# snc98_main_cpu.net
KiCad netlist of a schematic drawn in EAGLE
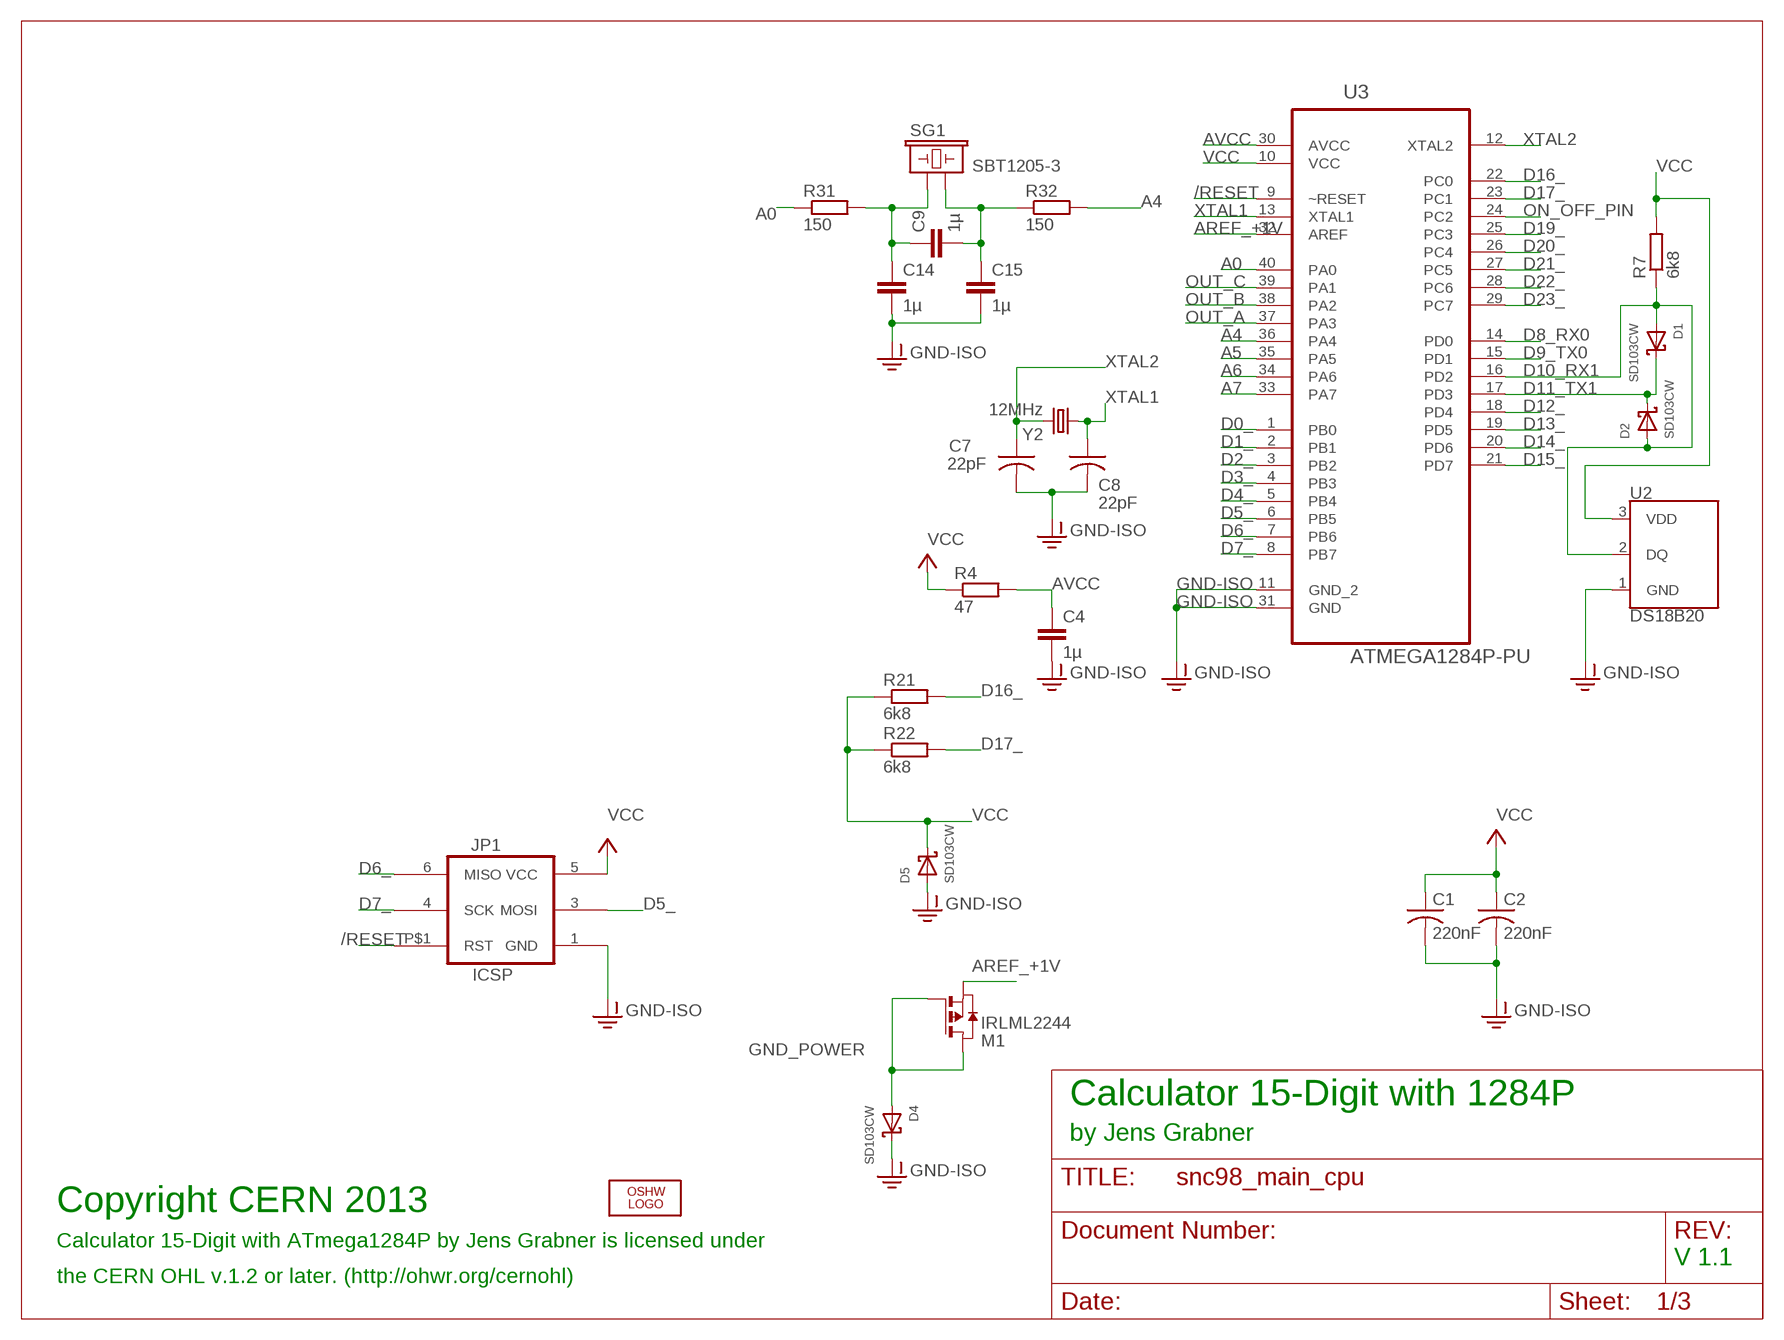
[diagram p0: schematic, sheet 1]
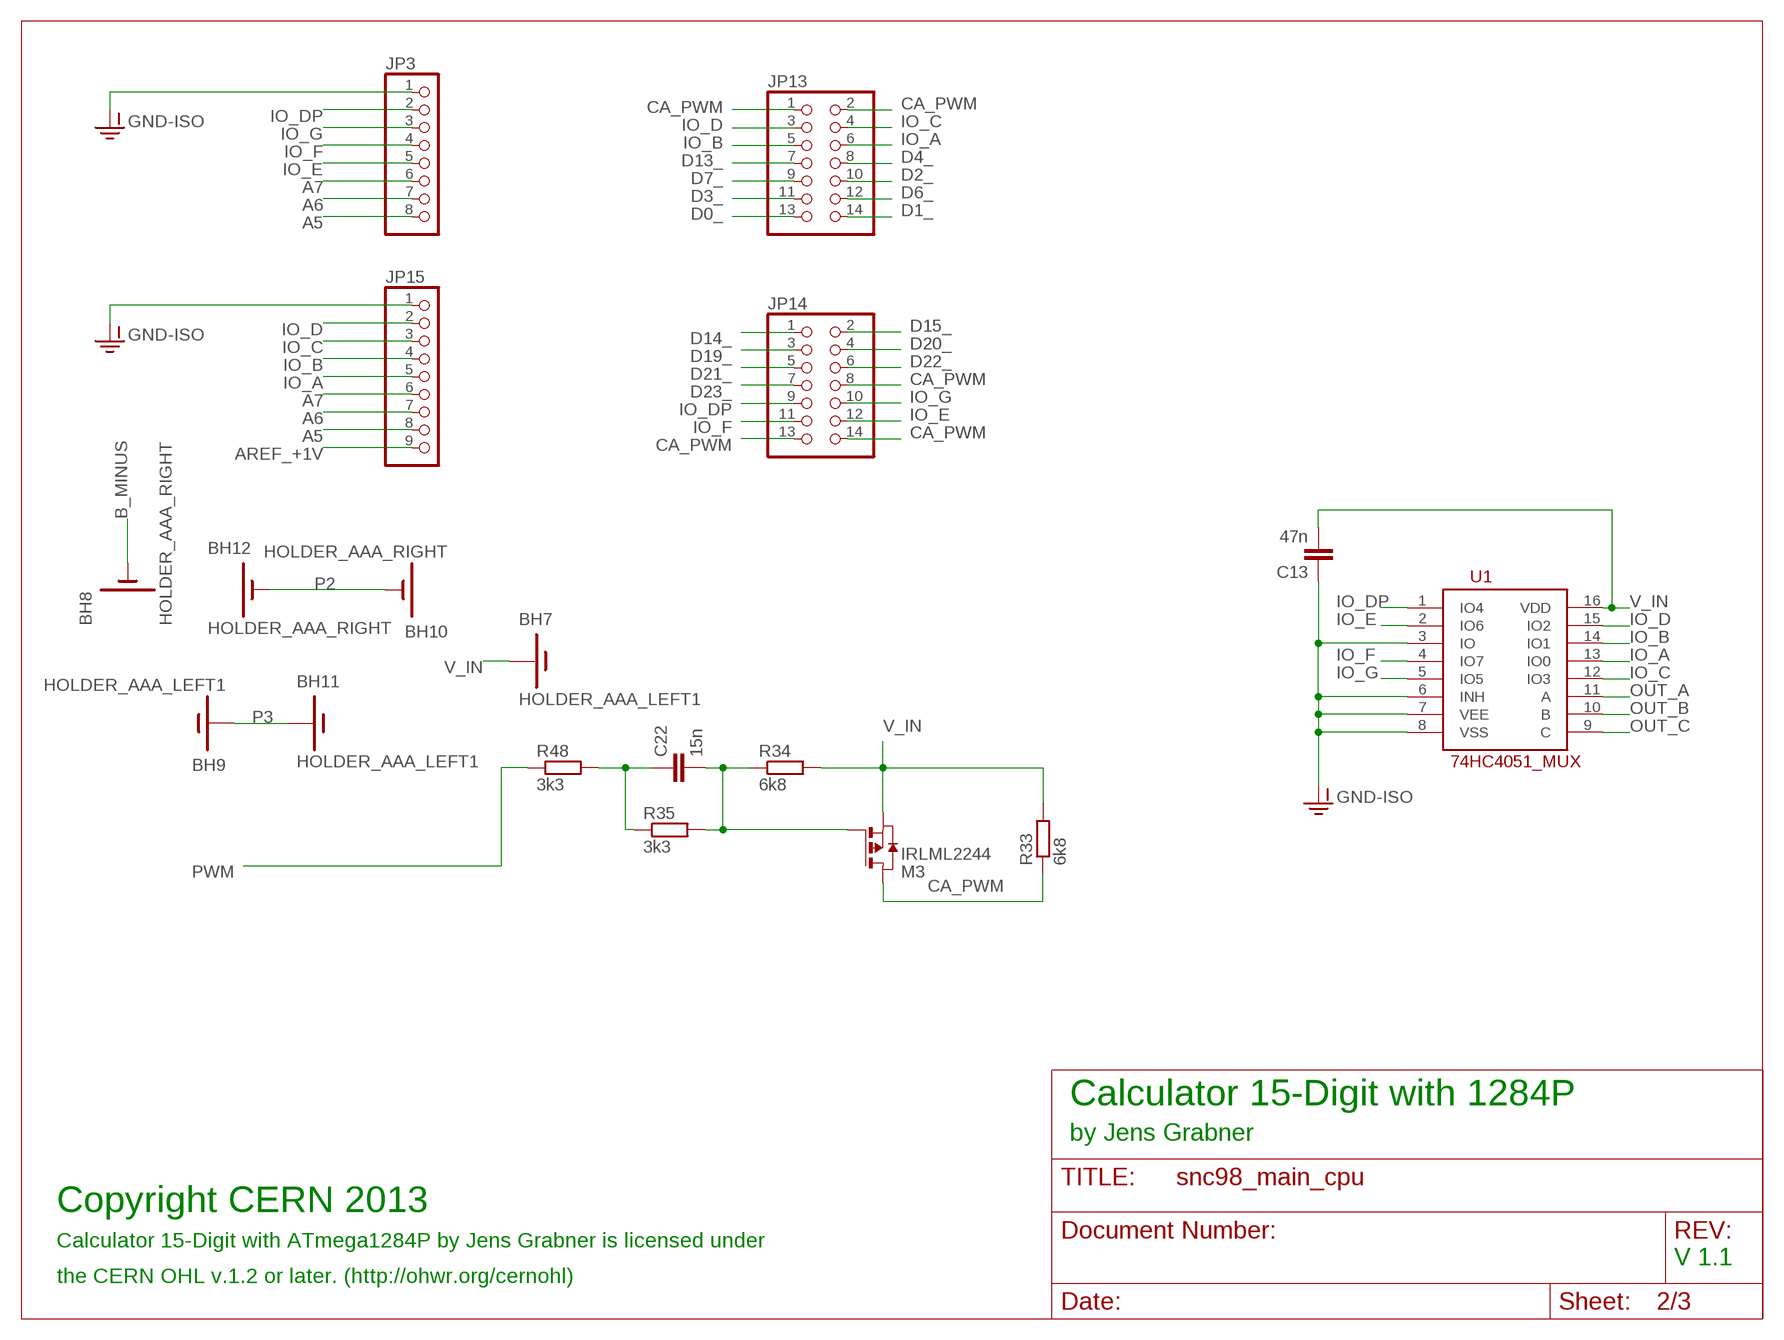
[diagram p1: schematic, sheet 2]
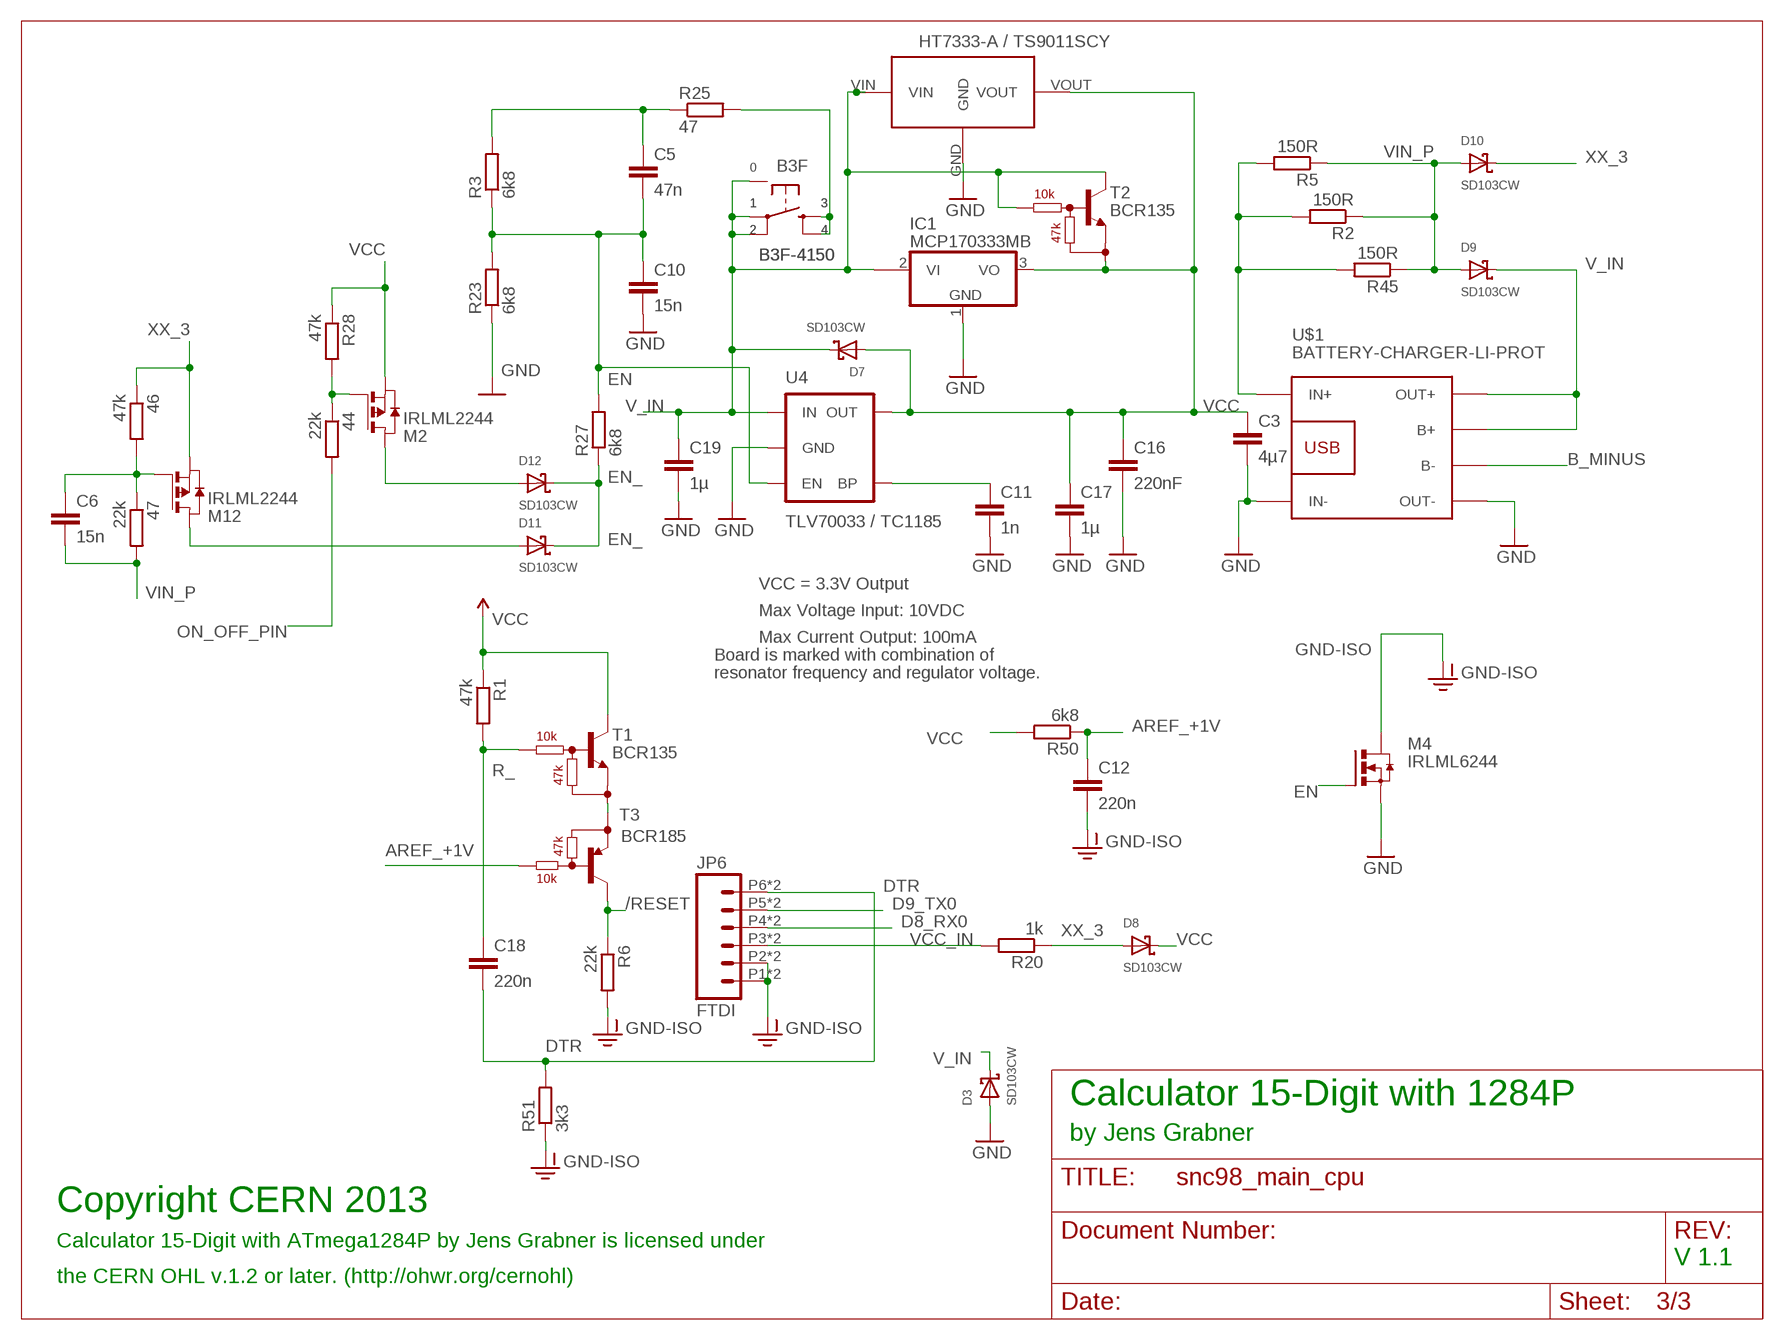
[diagram p2: schematic, sheet 3]

(export (version "E")
  (design (tool "Eeschema 10.0.6"))
  (components
    (comp (ref "44")
      (value "22k")
      (footprint "eagle-import:R1206")
      (libsource (lib "eagle-import") (part "R-EU_R1206"))
    )
    (comp (ref "46")
      (value "47k")
      (footprint "eagle-import:R1206")
      (libsource (lib "eagle-import") (part "R-EU_R1206"))
    )
    (comp (ref "47")
      (value "22k")
      (footprint "eagle-import:R1206")
      (libsource (lib "eagle-import") (part "R-EU_R1206"))
    )
    (comp (ref "C3")
      (value "4µ7")
      (footprint "eagle-import:C1206K")
      (libsource (lib "eagle-import") (part "C-EUC1206K"))
    )
    (comp (ref "C5")
      (value "47n")
      (footprint "eagle-import:C1206K")
      (fields (field (name "TME_EU") "CC0805KRX7R9473"))
      (libsource (lib "eagle-import") (part "C-EUC1206K"))
    )
    (comp (ref "C6")
      (value "15n")
      (footprint "eagle-import:C1206K")
      (fields (field (name "TME_EU") "CC0805KRX7R9153"))
      (libsource (lib "eagle-import") (part "C-EUC1206K"))
    )
    (comp (ref "C10")
      (value "15n")
      (footprint "eagle-import:C1206K")
      (fields (field (name "TME_EU") "CC0805KRX7R9153"))
      (libsource (lib "eagle-import") (part "C-EUC1206K"))
    )
    (comp (ref "C11")
      (value "1n")
      (footprint "eagle-import:0805")
      (libsource (lib "eagle-import") (part "CAP0805"))
    )
    (comp (ref "C12")
      (value "220n")
      (footprint "eagle-import:0805")
      (libsource (lib "eagle-import") (part "CAP0805"))
    )
    (comp (ref "C16")
      (value "220nF")
      (footprint "eagle-import:0805")
      (libsource (lib "eagle-import") (part "CAP0805"))
    )
    (comp (ref "C17")
      (value "1µ")
      (footprint "eagle-import:C1206K")
      (libsource (lib "eagle-import") (part "C-EUC1206K"))
    )
    (comp (ref "C18")
      (value "220n")
      (footprint "eagle-import:C1206K")
      (fields (field (name "TME_EU") "CC0805KPX7R7224"))
      (libsource (lib "eagle-import") (part "C-EUC1206K"))
    )
    (comp (ref "C19")
      (value "1µ")
      (footprint "eagle-import:C1206K")
      (libsource (lib "eagle-import") (part "C-EUC1206K"))
    )
    (comp (ref "D3")
      (value "SD103CW")
      (footprint "eagle-import:SOD-123F")
      (fields (field (name "MF") "MULTICOMP") (field (name "MPN") "SD103CW-7-F"))
      (libsource (lib "eagle-import") (part "DIODESOD-123F"))
    )
    (comp (ref "D7")
      (value "SD103CW")
      (footprint "eagle-import:SOD-123F")
      (fields (field (name "MF") "MULTICOMP") (field (name "MPN") "SD103CW-7-F"))
      (libsource (lib "eagle-import") (part "DIODESOD-123F"))
    )
    (comp (ref "D8")
      (value "SD103CW")
      (footprint "eagle-import:SOD-123F")
      (fields (field (name "MF") "MULTICOMP") (field (name "MPN") "SD103CW-7-F"))
      (libsource (lib "eagle-import") (part "DIODESOD-123F"))
    )
    (comp (ref "D9")
      (value "SD103CW")
      (footprint "eagle-import:SOD-123F")
      (fields (field (name "MF") "MULTICOMP") (field (name "MPN") "SD103CW-7-F"))
      (libsource (lib "eagle-import") (part "DIODESOD-123F"))
    )
    (comp (ref "D10")
      (value "SD103CW")
      (footprint "eagle-import:SOD-123F")
      (fields (field (name "MF") "MULTICOMP") (field (name "MPN") "SD103CW-7-F"))
      (libsource (lib "eagle-import") (part "DIODESOD-123F"))
    )
    (comp (ref "D11")
      (value "SD103CW")
      (footprint "eagle-import:SOD-123F")
      (fields (field (name "MF") "MULTICOMP") (field (name "MPN") "SD103CW-7-F"))
      (libsource (lib "eagle-import") (part "DIODESOD-123F"))
    )
    (comp (ref "D12")
      (value "SD103CW")
      (footprint "eagle-import:SOD-123F")
      (fields (field (name "MF") "MULTICOMP") (field (name "MPN") "SD103CW-7-F"))
      (libsource (lib "eagle-import") (part "DIODESOD-123F"))
    )
    (comp (ref "IC1")
      (value "MCP170333MB")
      (footprint "eagle-import:SOT89")
      (libsource (lib "eagle-import") (part "MCP1703MB33"))
    )
    (comp (ref "JP6")
      (value "FTDI")
      (footprint "eagle-import:1X06_LOCK")
      (libsource (lib "eagle-import") (part "M06LOCK"))
    )
    (comp (ref "M2")
      (value "IRLML2244")
      (footprint "eagle-import:SOT-23")
      (fields (field (name "MF") "INFINEON") (field (name "MPN") "IRLML2244TRPBF"))
      (libsource (lib "eagle-import") (part "IRLML6402"))
    )
    (comp (ref "M4")
      (value "IRLML6244")
      (footprint "eagle-import:SOT-23")
      (fields (field (name "MF") "INFINEON") (field (name "MPN") "IRLML6244TRPBF"))
      (libsource (lib "eagle-import") (part "IRLML2502M"))
    )
    (comp (ref "M12")
      (value "IRLML2244")
      (footprint "eagle-import:SOT-23")
      (fields (field (name "MF") "INFINEON") (field (name "MPN") "IRLML2244TRPBF"))
      (libsource (lib "eagle-import") (part "IRLML6402"))
    )
    (comp (ref "R1")
      (value "47k")
      (footprint "eagle-import:R1206")
      (libsource (lib "eagle-import") (part "R-EU_R1206"))
    )
    (comp (ref "R2")
      (value "150R")
      (footprint "eagle-import:0204_5")
      (libsource (lib "eagle-import") (part "R-EU_0204/5"))
    )
    (comp (ref "R3")
      (value "6k8")
      (footprint "eagle-import:R1206")
      (libsource (lib "eagle-import") (part "R-EU_R1206"))
    )
    (comp (ref "R5")
      (value "150R")
      (footprint "eagle-import:0207_10")
      (libsource (lib "eagle-import") (part "R-EU_0207/10"))
    )
    (comp (ref "R6")
      (value "22k")
      (footprint "eagle-import:R1206")
      (libsource (lib "eagle-import") (part "R-EU_R1206"))
    )
    (comp (ref "R20")
      (value "1k")
      (footprint "eagle-import:R1206")
      (libsource (lib "eagle-import") (part "R-EU_R1206"))
    )
    (comp (ref "R23")
      (value "6k8")
      (footprint "eagle-import:R1206")
      (libsource (lib "eagle-import") (part "R-EU_R1206"))
    )
    (comp (ref "R25")
      (value "47")
      (footprint "eagle-import:R1206")
      (libsource (lib "eagle-import") (part "R-EU_R1206"))
    )
    (comp (ref "R27")
      (value "6k8")
      (footprint "eagle-import:R1206")
      (libsource (lib "eagle-import") (part "R-EU_R1206"))
    )
    (comp (ref "R28")
      (value "47k")
      (footprint "eagle-import:R1206")
      (libsource (lib "eagle-import") (part "R-EU_R1206"))
    )
    (comp (ref "R45")
      (value "150R")
      (footprint "eagle-import:R1206")
      (libsource (lib "eagle-import") (part "R-EU_R1206"))
    )
    (comp (ref "R50")
      (value "6k8")
      (footprint "eagle-import:R1206")
      (libsource (lib "eagle-import") (part "R-EU_R1206"))
    )
    (comp (ref "R51")
      (value "3k3")
      (footprint "eagle-import:R1206")
      (libsource (lib "eagle-import") (part "R-EU_R1206"))
    )
    (comp (ref "S3")
      (value "B3F-4150")
      (footprint "eagle-import:TACTILE-PTH-12MM")
      (fields (field (name "MF") "OMRON") (field (name "MPN") "B3F4150"))
      (libsource (lib "eagle-import") (part "TACTILE_SWITCHTACTILE_SWITCH_PTH-12MM"))
    )
    (comp (ref "T1")
      (value "BCR135")
      (footprint "eagle-import:SOT23-BEC")
      (fields (field (name "MF") "INFINEON") (field (name "MPN") "BCR135E6327HTSA1"))
      (libsource (lib "eagle-import") (part "BCR135"))
    )
    (comp (ref "T2")
      (value "BCR135")
      (footprint "eagle-import:SOT23-BEC")
      (fields (field (name "MF") "INFINEON") (field (name "MPN") "BCR135E6327HTSA1"))
      (libsource (lib "eagle-import") (part "BCR135"))
    )
    (comp (ref "T3")
      (value "BCR185")
      (footprint "eagle-import:SOT23-R_INFINEON")
      (fields (field (name "MF") "ROHM") (field (name "MPN") "DTA114YKAT146"))
      (libsource (lib "eagle-import") (part "BCR185"))
    )
    (comp (ref "U$1")
      (value "BATTERY-CHARGER-LI-PROT")
      (footprint "eagle-import:BATTERY-CHARGER-LI-PROT")
      (libsource (lib "eagle-import") (part "BATTERY-CHARGER-LI-PROT"))
    )
    (comp (ref "U$3")
      (value "HT7333 / TS9011SCY")
      (footprint "eagle-import:SOT89")
      (libsource (lib "eagle-import") (part "HT7333"))
    )
    (comp (ref "U4")
      (value "TLV70033 / TC1185")
      (footprint "eagle-import:SOT23-5")
      (libsource (lib "eagle-import") (part "V_REG_LDOSMD"))
    )
    (comp (ref "C1")
      (value "220nF")
      (footprint "eagle-import:C1206K")
      (libsource (lib "eagle-import") (part "C-USC1206K"))
    )
    (comp (ref "C2")
      (value "220nF")
      (footprint "eagle-import:C1206K")
      (libsource (lib "eagle-import") (part "C-USC1206K"))
    )
    (comp (ref "C4")
      (value "1µ")
      (footprint "eagle-import:C1206K")
      (libsource (lib "eagle-import") (part "C-EUC1206K"))
    )
    (comp (ref "C7")
      (value "22pF")
      (footprint "eagle-import:C0805K")
      (libsource (lib "eagle-import") (part "C-USC0805K"))
    )
    (comp (ref "C8")
      (value "22pF")
      (footprint "eagle-import:C0805K")
      (libsource (lib "eagle-import") (part "C-USC0805K"))
    )
    (comp (ref "C9")
      (value "1µ")
      (footprint "eagle-import:C1206K")
      (libsource (lib "eagle-import") (part "C-EUC1206K"))
    )
    (comp (ref "C14")
      (value "1µ")
      (footprint "eagle-import:C1206K")
      (libsource (lib "eagle-import") (part "C-EUC1206K"))
    )
    (comp (ref "C15")
      (value "1µ")
      (footprint "eagle-import:C1206K")
      (libsource (lib "eagle-import") (part "C-EUC1206K"))
    )
    (comp (ref "D1")
      (value "SD103CW")
      (footprint "eagle-import:SOD-323")
      (fields (field (name "MF") "MULTICOMP") (field (name "MPN") "SD103CW-7-F"))
      (libsource (lib "eagle-import") (part "DIODESOD-323"))
    )
    (comp (ref "D2")
      (value "SD103CW")
      (footprint "eagle-import:SOD-123")
      (fields (field (name "MF") "MULTICOMP") (field (name "MPN") "SD103CW-7-F"))
      (libsource (lib "eagle-import") (part "DIODESOD-123"))
    )
    (comp (ref "D4")
      (value "SD103CW")
      (footprint "eagle-import:SOD-123F")
      (fields (field (name "MF") "MULTICOMP") (field (name "MPN") "SD103CW-7-F"))
      (libsource (lib "eagle-import") (part "DIODESOD-123F"))
    )
    (comp (ref "D5")
      (value "SD103CW")
      (footprint "eagle-import:SOD-123F")
      (fields (field (name "MF") "MULTICOMP") (field (name "MPN") "SD103CW-7-F"))
      (libsource (lib "eagle-import") (part "DIODESOD-123F"))
    )
    (comp (ref "JP1")
      (value "ICSP")
      (footprint "eagle-import:2X3_SMD_VERTICAL")
      (libsource (lib "eagle-import") (part "AVR_SPI_PRG_6"))
    )
    (comp (ref "LOGO1")
      (value "OSHW_LOGO_8MILX0150-NT")
      (footprint "eagle-import:OSHW_8X150_NOTEXT")
      (libsource (lib "eagle-import") (part "OSHW_LOGO_8MILX0150-NT"))
    )
    (comp (ref "M1")
      (value "IRLML2244")
      (footprint "eagle-import:SOT-23")
      (fields
        (field (name "MF") "INFINEON")
        (field (name "MPN") "IRLML2244TRPBF")
        (field (name "TME_EU") "DMG2305UX-7")
      )
      (libsource (lib "eagle-import") (part "IRLML6402"))
    )
    (comp (ref "R4")
      (value "47")
      (footprint "eagle-import:R1206")
      (libsource (lib "eagle-import") (part "R-EU_R1206"))
    )
    (comp (ref "R7")
      (value "6k8")
      (footprint "eagle-import:R1206")
      (libsource (lib "eagle-import") (part "R-EU_R1206"))
    )
    (comp (ref "R21")
      (value "6k8")
      (footprint "eagle-import:R1206")
      (libsource (lib "eagle-import") (part "R-EU_R1206"))
    )
    (comp (ref "R22")
      (value "6k8")
      (footprint "eagle-import:R1206")
      (libsource (lib "eagle-import") (part "R-EU_R1206"))
    )
    (comp (ref "R31")
      (value "150")
      (footprint "eagle-import:R1206")
      (libsource (lib "eagle-import") (part "R-EU_R1206"))
    )
    (comp (ref "R32")
      (value "150")
      (footprint "eagle-import:R1206")
      (libsource (lib "eagle-import") (part "R-EU_R1206"))
    )
    (comp (ref "SG1")
      (value "SBT1205-3")
      (footprint "eagle-import:BUZZER-12MM-NS")
      (libsource (lib "eagle-import") (part "BUZZERNS"))
    )
    (comp (ref "U2")
      (value "DS18B20")
      (footprint "eagle-import:TO-92-AMMO")
      (libsource (lib "eagle-import") (part "DS18B20"))
    )
    (comp (ref "U3")
      (value "ATMEGA1284P-PU")
      (footprint "eagle-import:DIP254P1524X483-40")
      (fields (field (name "MF") "MICROCHIP"))
      (libsource (lib "eagle-import") (part "ATMEGA1284P-PU"))
    )
    (comp (ref "Y2")
      (value "12MHz")
      (footprint "eagle-import:HC49U-V")
      (libsource (lib "eagle-import") (part "CRYSTALHC49UV"))
    )
    (comp (ref "BH7")
      (value "HOLDER_AAA_LEFT1")
      (footprint "eagle-import:BATTERY-AAA-LEFT")
      (libsource (lib "eagle-import") (part "HOLDER_AAA_LEFT1"))
    )
    (comp (ref "BH8")
      (value "HOLDER_AAA_RIGHT")
      (footprint "eagle-import:BATTERY-AAA-RIGHT")
      (libsource (lib "eagle-import") (part "HOLDER_AAA_RIGHT"))
    )
    (comp (ref "BH9")
      (value "HOLDER_AAA_LEFT1")
      (footprint "eagle-import:BATTERY-AAA-LEFT")
      (fields (field (name "TME_EU") "BC-0401"))
      (libsource (lib "eagle-import") (part "HOLDER_AAA_LEFT1"))
    )
    (comp (ref "BH10")
      (value "HOLDER_AAA_RIGHT")
      (footprint "eagle-import:BATTERY-AAA-RIGHT")
      (libsource (lib "eagle-import") (part "HOLDER_AAA_RIGHT"))
    )
    (comp (ref "BH11")
      (value "HOLDER_AAA_LEFT1")
      (footprint "eagle-import:BATTERY-AAA-LEFT")
      (libsource (lib "eagle-import") (part "HOLDER_AAA_LEFT1"))
    )
    (comp (ref "BH12")
      (value "HOLDER_AAA_RIGHT")
      (footprint "eagle-import:BATTERY-AAA-RIGHT")
      (libsource (lib "eagle-import") (part "HOLDER_AAA_RIGHT"))
    )
    (comp (ref "C13")
      (value "47n")
      (footprint "eagle-import:C1206K")
      (fields (field (name "TME_EU") "CC0805KRX7R9473"))
      (libsource (lib "eagle-import") (part "C-EUC1206K"))
    )
    (comp (ref "C22")
      (value "15n")
      (footprint "eagle-import:C1206K")
      (fields (field (name "TME_EU") "CC0805KRX7R9153"))
      (libsource (lib "eagle-import") (part "C-EUC1206K"))
    )
    (comp (ref "JP3")
      (value "PINHD-1X8CLEANBIG")
      (footprint "eagle-import:1X08-CLEANBIG")
      (libsource (lib "eagle-import") (part "PINHD-1X8CLEANBIG"))
    )
    (comp (ref "JP13")
      (value "PINHD-2X7")
      (footprint "eagle-import:2X07")
      (libsource (lib "eagle-import") (part "PINHD-2X7"))
    )
    (comp (ref "JP14")
      (value "PINHD-2X7")
      (footprint "eagle-import:2X07")
      (libsource (lib "eagle-import") (part "PINHD-2X7"))
    )
    (comp (ref "JP15")
      (value "PINHD-1X9")
      (footprint "eagle-import:1X09-BIG")
      (libsource (lib "eagle-import") (part "PINHD-1X9"))
    )
    (comp (ref "M3")
      (value "IRLML2244")
      (footprint "eagle-import:SOT-23")
      (fields (field (name "MF") "INFINEON") (field (name "MPN") "IRLML2244TRPBF"))
      (libsource (lib "eagle-import") (part "IRLML6402"))
    )
    (comp (ref "R33")
      (value "6k8")
      (footprint "eagle-import:R1206")
      (libsource (lib "eagle-import") (part "R-EU_R1206"))
    )
    (comp (ref "R34")
      (value "6k8")
      (footprint "eagle-import:R1206")
      (libsource (lib "eagle-import") (part "R-EU_R1206"))
    )
    (comp (ref "R35")
      (value "3k3")
      (footprint "eagle-import:R1206")
      (libsource (lib "eagle-import") (part "R-EU_R1206"))
    )
    (comp (ref "R48")
      (value "3k3")
      (footprint "eagle-import:R1206")
      (libsource (lib "eagle-import") (part "R-EU_R1206"))
    )
    (comp (ref "U1")
      (value "74HC4051_MUX")
      (footprint "eagle-import:SO16")
      (libsource (lib "eagle-import") (part "74HC4051_MUX"))
    )
  )
  (nets
    (net (code "1") (name "A0") (class "Default")
      (node (ref "R31") (pin "1") (pinfunction "1_1") (pintype "passive"))
      (node (ref "U3") (pin "40") (pinfunction "PA0_40") (pintype "bidirectional"))
    )
    (net (code "2") (name "A4") (class "Default")
      (node (ref "R32") (pin "2") (pinfunction "2_2") (pintype "passive"))
      (node (ref "U3") (pin "36") (pinfunction "PA4_36") (pintype "bidirectional"))
    )
    (net (code "3") (name "A5") (class "Default")
      (node (ref "JP15") (pin "8") (pinfunction "8_8") (pintype "passive"))
      (node (ref "JP3") (pin "8") (pinfunction "8_8") (pintype "passive"))
      (node (ref "U3") (pin "35") (pinfunction "PA5_35") (pintype "bidirectional"))
    )
    (net (code "4") (name "A6") (class "Default")
      (node (ref "JP15") (pin "7") (pinfunction "7_7") (pintype "passive"))
      (node (ref "JP3") (pin "7") (pinfunction "7_7") (pintype "passive"))
      (node (ref "U3") (pin "34") (pinfunction "PA6_34") (pintype "bidirectional"))
    )
    (net (code "5") (name "A7") (class "Default")
      (node (ref "JP15") (pin "6") (pinfunction "6_6") (pintype "passive"))
      (node (ref "JP3") (pin "6") (pinfunction "6_6") (pintype "passive"))
      (node (ref "U3") (pin "33") (pinfunction "PA7_33") (pintype "bidirectional"))
    )
    (net (code "6") (name "AREF_+1V") (class "Default")
      (node (ref "C12") (pin "3") (pinfunction "1_3") (pintype "passive"))
      (node (ref "JP15") (pin "9") (pinfunction "9_9") (pintype "passive"))
      (node (ref "M1") (pin "2") (pinfunction "S_2") (pintype "passive"))
      (node (ref "R50") (pin "1") (pinfunction "1_1") (pintype "passive"))
      (node (ref "T3") (pin "B") (pinfunction "B_B") (pintype "passive"))
      (node (ref "U3") (pin "32") (pinfunction "AREF_32") (pintype "input"))
    )
    (net (code "7") (name "AVCC") (class "Default")
      (node (ref "C4") (pin "1") (pinfunction "1_1") (pintype "passive"))
      (node (ref "R4") (pin "2") (pinfunction "2_2") (pintype "passive"))
      (node (ref "U3") (pin "30") (pinfunction "AVCC_30") (pintype "power_in"))
    )
    (net (code "8") (name "B_MINUS") (class "Default")
      (node (ref "BH8") (pin "M1") (pinfunction "-_M1") (pintype "power_in"))
      (node (ref "BH8") (pin "M2") (pinfunction "-_M2") (pintype "power_in"))
      (node (ref "BH8") (pin "M3") (pinfunction "-_M3") (pintype "power_in"))
      (node (ref "BH8") (pin "M4") (pinfunction "-_M4") (pintype "power_in"))
      (node (ref "U$1") (pin "B-") (pinfunction "B-_B-") (pintype "bidirectional"))
    )
    (net (code "9") (name "CA_PWM") (class "Default")
      (node (ref "JP13") (pin "1") (pinfunction "1_1") (pintype "passive"))
      (node (ref "JP13") (pin "2") (pinfunction "2_2") (pintype "passive"))
      (node (ref "JP14") (pin "13") (pinfunction "13_13") (pintype "passive"))
      (node (ref "JP14") (pin "14") (pinfunction "14_14") (pintype "passive"))
      (node (ref "JP14") (pin "8") (pinfunction "8_8") (pintype "passive"))
      (node (ref "M3") (pin "3") (pinfunction "D_3") (pintype "passive"))
      (node (ref "R33") (pin "1") (pinfunction "1_1") (pintype "passive"))
    )
    (net (code "10") (name "D0_") (class "Default")
      (node (ref "JP13") (pin "13") (pinfunction "13_13") (pintype "passive"))
      (node (ref "U3") (pin "1") (pinfunction "PB0_1") (pintype "bidirectional"))
    )
    (net (code "11") (name "D1_") (class "Default")
      (node (ref "JP13") (pin "14") (pinfunction "14_14") (pintype "passive"))
      (node (ref "U3") (pin "2") (pinfunction "PB1_2") (pintype "bidirectional"))
    )
    (net (code "12") (name "D2_") (class "Default")
      (node (ref "JP13") (pin "10") (pinfunction "10_10") (pintype "passive"))
      (node (ref "U3") (pin "3") (pinfunction "PB2_3") (pintype "bidirectional"))
    )
    (net (code "13") (name "D3_") (class "Default")
      (node (ref "JP13") (pin "11") (pinfunction "11_11") (pintype "passive"))
      (node (ref "U3") (pin "4") (pinfunction "PB3_4") (pintype "bidirectional"))
    )
    (net (code "14") (name "D4_") (class "Default")
      (node (ref "JP13") (pin "8") (pinfunction "8_8") (pintype "passive"))
      (node (ref "U3") (pin "5") (pinfunction "PB4_5") (pintype "bidirectional"))
    )
    (net (code "15") (name "D5_") (class "Default")
      (node (ref "JP1") (pin "3") (pinfunction "MOSI_3") (pintype "passive"))
      (node (ref "U3") (pin "6") (pinfunction "PB5_6") (pintype "bidirectional"))
    )
    (net (code "16") (name "D6_") (class "Default")
      (node (ref "JP1") (pin "6") (pinfunction "MISO_6") (pintype "passive"))
      (node (ref "JP13") (pin "12") (pinfunction "12_12") (pintype "passive"))
      (node (ref "U3") (pin "7") (pinfunction "PB6_7") (pintype "bidirectional"))
    )
    (net (code "17") (name "D7_") (class "Default")
      (node (ref "JP1") (pin "4") (pinfunction "SCK_4") (pintype "passive"))
      (node (ref "JP13") (pin "9") (pinfunction "9_9") (pintype "passive"))
      (node (ref "U3") (pin "8") (pinfunction "PB7_8") (pintype "bidirectional"))
    )
    (net (code "18") (name "D8_RX0") (class "Default")
      (node (ref "JP6") (pin "P4") (pinfunction "4_P4") (pintype "passive"))
      (node (ref "JP6") (pin "P4A") (pinfunction "4_P4A") (pintype "passive"))
      (node (ref "U3") (pin "14") (pinfunction "PD0_14") (pintype "bidirectional"))
    )
    (net (code "19") (name "D9_TX0") (class "Default")
      (node (ref "JP6") (pin "P5") (pinfunction "5_P5") (pintype "passive"))
      (node (ref "JP6") (pin "P5A") (pinfunction "5_P5A") (pintype "passive"))
      (node (ref "U3") (pin "15") (pinfunction "PD1_15") (pintype "bidirectional"))
    )
    (net (code "20") (name "D10_RX1") (class "Default")
      (node (ref "D1") (pin "A") (pinfunction "A_A") (pintype "passive"))
      (node (ref "D2") (pin "A") (pinfunction "A_A") (pintype "passive"))
      (node (ref "R7") (pin "1") (pinfunction "1_1") (pintype "passive"))
      (node (ref "U2") (pin "2") (pinfunction "DQ_2") (pintype "bidirectional"))
      (node (ref "U3") (pin "16") (pinfunction "PD2_16") (pintype "bidirectional"))
    )
    (net (code "21") (name "D11_TX1") (class "Default")
      (node (ref "D1") (pin "C") (pinfunction "C_C") (pintype "passive"))
      (node (ref "D2") (pin "C") (pinfunction "C_C") (pintype "passive"))
      (node (ref "U3") (pin "17") (pinfunction "PD3_17") (pintype "bidirectional"))
    )
    (net (code "22") (name "D12_") (class "Default")
      (node (ref "U3") (pin "18") (pinfunction "PD4_18") (pintype "bidirectional"))
    )
    (net (code "23") (name "D13_") (class "Default")
      (node (ref "JP13") (pin "7") (pinfunction "7_7") (pintype "passive"))
      (node (ref "U3") (pin "19") (pinfunction "PD5_19") (pintype "bidirectional"))
    )
    (net (code "24") (name "D14_") (class "Default")
      (node (ref "JP14") (pin "1") (pinfunction "1_1") (pintype "passive"))
      (node (ref "U3") (pin "20") (pinfunction "PD6_20") (pintype "bidirectional"))
    )
    (net (code "25") (name "D15_") (class "Default")
      (node (ref "JP14") (pin "2") (pinfunction "2_2") (pintype "passive"))
      (node (ref "U3") (pin "21") (pinfunction "PD7_21") (pintype "bidirectional"))
    )
    (net (code "26") (name "D16_") (class "Default")
      (node (ref "R21") (pin "2") (pinfunction "2_2") (pintype "passive"))
      (node (ref "U3") (pin "22") (pinfunction "PC0_22") (pintype "bidirectional"))
    )
    (net (code "27") (name "D17_") (class "Default")
      (node (ref "R22") (pin "2") (pinfunction "2_2") (pintype "passive"))
      (node (ref "U3") (pin "23") (pinfunction "PC1_23") (pintype "bidirectional"))
    )
    (net (code "28") (name "D19_") (class "Default")
      (node (ref "JP14") (pin "3") (pinfunction "3_3") (pintype "passive"))
      (node (ref "U3") (pin "25") (pinfunction "PC3_25") (pintype "bidirectional"))
    )
    (net (code "29") (name "D20_") (class "Default")
      (node (ref "JP14") (pin "4") (pinfunction "4_4") (pintype "passive"))
      (node (ref "U3") (pin "26") (pinfunction "PC4_26") (pintype "bidirectional"))
    )
    (net (code "30") (name "D21_") (class "Default")
      (node (ref "JP14") (pin "5") (pinfunction "5_5") (pintype "passive"))
      (node (ref "U3") (pin "27") (pinfunction "PC5_27") (pintype "bidirectional"))
    )
    (net (code "31") (name "D22_") (class "Default")
      (node (ref "JP14") (pin "6") (pinfunction "6_6") (pintype "passive"))
      (node (ref "U3") (pin "28") (pinfunction "PC6_28") (pintype "bidirectional"))
    )
    (net (code "32") (name "D23_") (class "Default")
      (node (ref "JP14") (pin "7") (pinfunction "7_7") (pintype "passive"))
      (node (ref "U3") (pin "29") (pinfunction "PC7_29") (pintype "bidirectional"))
    )
    (net (code "33") (name "DTR") (class "Default")
      (node (ref "C18") (pin "2") (pinfunction "2_2") (pintype "passive"))
      (node (ref "JP6") (pin "P6") (pinfunction "6_P6") (pintype "passive"))
      (node (ref "JP6") (pin "P6A") (pinfunction "6_P6A") (pintype "passive"))
      (node (ref "R51") (pin "2") (pinfunction "2_2") (pintype "passive"))
    )
    (net (code "34") (name "EN") (class "Default")
      (node (ref "C10") (pin "1") (pinfunction "1_1") (pintype "passive"))
      (node (ref "C5") (pin "2") (pinfunction "2_2") (pintype "passive"))
      (node (ref "M4") (pin "1") (pinfunction "G_1") (pintype "passive"))
      (node (ref "R23") (pin "2") (pinfunction "2_2") (pintype "passive"))
      (node (ref "R27") (pin "2") (pinfunction "2_2") (pintype "passive"))
      (node (ref "R3") (pin "1") (pinfunction "1_1") (pintype "passive"))
      (node (ref "U4") (pin "3") (pinfunction "EN_3") (pintype "input"))
    )
    (net (code "35") (name "EN_") (class "Default")
      (node (ref "D11") (pin "C") (pinfunction "C_C") (pintype "passive"))
      (node (ref "D12") (pin "C") (pinfunction "C_C") (pintype "passive"))
      (node (ref "R27") (pin "1") (pinfunction "1_1") (pintype "passive"))
    )
    (net (code "36") (name "GND") (class "Default")
      (node (ref "C10") (pin "2") (pinfunction "2_2") (pintype "passive"))
      (node (ref "C11") (pin "4") (pinfunction "2_4") (pintype "passive"))
      (node (ref "C16") (pin "4") (pinfunction "2_4") (pintype "passive"))
      (node (ref "C17") (pin "2") (pinfunction "2_2") (pintype "passive"))
      (node (ref "C19") (pin "2") (pinfunction "2_2") (pintype "passive"))
      (node (ref "C3") (pin "2") (pinfunction "2_2") (pintype "passive"))
      (node (ref "D3") (pin "A") (pinfunction "A_A") (pintype "passive"))
      (node (ref "IC1") (pin "1") (pinfunction "GND_1") (pintype "passive"))
      (node (ref "M4") (pin "2") (pinfunction "S_2") (pintype "passive"))
      (node (ref "R23") (pin "1") (pinfunction "1_1") (pintype "passive"))
      (node (ref "U$1") (pin "IN-") (pinfunction "IN-_IN-") (pintype "bidirectional"))
      (node (ref "U$1") (pin "OUT-") (pinfunction "OUT-_OUT-") (pintype "bidirectional"))
      (node (ref "U$3") (pin "GND") (pinfunction "GND_GND") (pintype "bidirectional"))
      (node (ref "U4") (pin "2") (pinfunction "GND_2") (pintype "input"))
    )
    (net (code "37") (name "GND-ISO") (class "Default")
      (node (ref "C1") (pin "2") (pinfunction "2_2") (pintype "passive"))
      (node (ref "C12") (pin "4") (pinfunction "2_4") (pintype "passive"))
      (node (ref "C13") (pin "1") (pinfunction "1_1") (pintype "passive"))
      (node (ref "C14") (pin "2") (pinfunction "2_2") (pintype "passive"))
      (node (ref "C15") (pin "2") (pinfunction "2_2") (pintype "passive"))
      (node (ref "C2") (pin "2") (pinfunction "2_2") (pintype "passive"))
      (node (ref "C4") (pin "2") (pinfunction "2_2") (pintype "passive"))
      (node (ref "C7") (pin "2") (pinfunction "2_2") (pintype "passive"))
      (node (ref "C8") (pin "2") (pinfunction "2_2") (pintype "passive"))
      (node (ref "D4") (pin "C") (pinfunction "C_C") (pintype "passive"))
      (node (ref "D5") (pin "A") (pinfunction "A_A") (pintype "passive"))
      (node (ref "JP1") (pin "1") (pinfunction "GND_1") (pintype "passive"))
      (node (ref "JP15") (pin "1") (pinfunction "1_1") (pintype "passive"))
      (node (ref "JP3") (pin "1") (pinfunction "1_1") (pintype "passive"))
      (node (ref "JP6") (pin "P1") (pinfunction "1_P1") (pintype "passive"))
      (node (ref "JP6") (pin "P1A") (pinfunction "1_P1A") (pintype "passive"))
      (node (ref "JP6") (pin "P2") (pinfunction "2_P2") (pintype "passive"))
      (node (ref "JP6") (pin "P2A") (pinfunction "2_P2A") (pintype "passive"))
      (node (ref "M4") (pin "3") (pinfunction "D_3") (pintype "passive"))
      (node (ref "R51") (pin "1") (pinfunction "1_1") (pintype "passive"))
      (node (ref "R6") (pin "2") (pinfunction "2_2") (pintype "passive"))
      (node (ref "U1") (pin "3") (pinfunction "IO_3") (pintype "bidirectional"))
      (node (ref "U1") (pin "6") (pinfunction "INH_6") (pintype "bidirectional"))
      (node (ref "U1") (pin "7") (pinfunction "VEE_7") (pintype "bidirectional"))
      (node (ref "U1") (pin "8") (pinfunction "VSS_8") (pintype "bidirectional"))
      (node (ref "U2") (pin "1") (pinfunction "GND_1") (pintype "power_in"))
      (node (ref "U3") (pin "11") (pinfunction "GND_2_11") (pintype "passive"))
      (node (ref "U3") (pin "31") (pinfunction "GND_31") (pintype "passive"))
    )
    (net (code "38") (name "GND_POWER") (class "Default")
      (node (ref "D4") (pin "A") (pinfunction "A_A") (pintype "passive"))
      (node (ref "M1") (pin "1") (pinfunction "G_1") (pintype "passive"))
      (node (ref "M1") (pin "3") (pinfunction "D_3") (pintype "passive"))
    )
    (net (code "39") (name "IO_A") (class "Default")
      (node (ref "JP13") (pin "6") (pinfunction "6_6") (pintype "passive"))
      (node (ref "JP15") (pin "5") (pinfunction "5_5") (pintype "passive"))
      (node (ref "U1") (pin "13") (pinfunction "IO0_13") (pintype "bidirectional"))
    )
    (net (code "40") (name "IO_B") (class "Default")
      (node (ref "JP13") (pin "5") (pinfunction "5_5") (pintype "passive"))
      (node (ref "JP15") (pin "4") (pinfunction "4_4") (pintype "passive"))
      (node (ref "U1") (pin "14") (pinfunction "IO1_14") (pintype "bidirectional"))
    )
    (net (code "41") (name "IO_C") (class "Default")
      (node (ref "JP13") (pin "4") (pinfunction "4_4") (pintype "passive"))
      (node (ref "JP15") (pin "3") (pinfunction "3_3") (pintype "passive"))
      (node (ref "U1") (pin "12") (pinfunction "IO3_12") (pintype "bidirectional"))
    )
    (net (code "42") (name "IO_D") (class "Default")
      (node (ref "JP13") (pin "3") (pinfunction "3_3") (pintype "passive"))
      (node (ref "JP15") (pin "2") (pinfunction "2_2") (pintype "passive"))
      (node (ref "U1") (pin "15") (pinfunction "IO2_15") (pintype "bidirectional"))
    )
    (net (code "43") (name "IO_DP") (class "Default")
      (node (ref "JP14") (pin "9") (pinfunction "9_9") (pintype "passive"))
      (node (ref "JP3") (pin "2") (pinfunction "2_2") (pintype "passive"))
      (node (ref "U1") (pin "1") (pinfunction "IO4_1") (pintype "bidirectional"))
    )
    (net (code "44") (name "IO_E") (class "Default")
      (node (ref "JP14") (pin "12") (pinfunction "12_12") (pintype "passive"))
      (node (ref "JP3") (pin "5") (pinfunction "5_5") (pintype "passive"))
      (node (ref "U1") (pin "2") (pinfunction "IO6_2") (pintype "bidirectional"))
    )
    (net (code "45") (name "IO_F") (class "Default")
      (node (ref "JP14") (pin "11") (pinfunction "11_11") (pintype "passive"))
      (node (ref "JP3") (pin "4") (pinfunction "4_4") (pintype "passive"))
      (node (ref "U1") (pin "4") (pinfunction "IO7_4") (pintype "bidirectional"))
    )
    (net (code "46") (name "IO_G") (class "Default")
      (node (ref "JP14") (pin "10") (pinfunction "10_10") (pintype "passive"))
      (node (ref "JP3") (pin "3") (pinfunction "3_3") (pintype "passive"))
      (node (ref "U1") (pin "5") (pinfunction "IO5_5") (pintype "bidirectional"))
    )
    (net (code "47") (name "Net-(C5-Pad1)") (class "Default")
      (node (ref "C5") (pin "1") (pinfunction "1_1") (pintype "passive"))
      (node (ref "R25") (pin "1") (pinfunction "1_1") (pintype "passive"))
      (node (ref "R3") (pin "2") (pinfunction "2_2") (pintype "passive"))
    )
    (net (code "48") (name "Net-(C11-1)") (class "Default")
      (node (ref "C11") (pin "3") (pinfunction "1_3") (pintype "passive"))
      (node (ref "U4") (pin "4") (pinfunction "BP_4") (pintype "input"))
    )
    (net (code "49") (name "Net-(C22-Pad1)") (class "Default")
      (node (ref "C22") (pin "1") (pinfunction "1_1") (pintype "passive"))
      (node (ref "R35") (pin "1") (pinfunction "1_1") (pintype "passive"))
      (node (ref "R48") (pin "2") (pinfunction "2_2") (pintype "passive"))
    )
    (net (code "50") (name "Net-(M2-D)") (class "Default")
      (node (ref "D12") (pin "A") (pinfunction "A_A") (pintype "passive"))
      (node (ref "M2") (pin "3") (pinfunction "D_3") (pintype "passive"))
    )
    (net (code "51") (name "Net-(M2-G)") (class "Default")
      (node (ref "44") (pin "1") (pinfunction "1_1") (pintype "passive"))
      (node (ref "M2") (pin "1") (pinfunction "G_1") (pintype "passive"))
      (node (ref "R28") (pin "2") (pinfunction "2_2") (pintype "passive"))
    )
    (net (code "52") (name "Net-(M3-G)") (class "Default")
      (node (ref "C22") (pin "2") (pinfunction "2_2") (pintype "passive"))
      (node (ref "M3") (pin "1") (pinfunction "G_1") (pintype "passive"))
      (node (ref "R34") (pin "1") (pinfunction "1_1") (pintype "passive"))
      (node (ref "R35") (pin "2") (pinfunction "2_2") (pintype "passive"))
    )
    (net (code "53") (name "Net-(M12-D)") (class "Default")
      (node (ref "D11") (pin "A") (pinfunction "A_A") (pintype "passive"))
      (node (ref "M12") (pin "3") (pinfunction "D_3") (pintype "passive"))
    )
    (net (code "54") (name "Net-(M12-G)") (class "Default")
      (node (ref "46") (pin "2") (pinfunction "2_2") (pintype "passive"))
      (node (ref "47") (pin "1") (pinfunction "1_1") (pintype "passive"))
      (node (ref "C6") (pin "1") (pinfunction "1_1") (pintype "passive"))
      (node (ref "M12") (pin "1") (pinfunction "G_1") (pintype "passive"))
    )
    (net (code "55") (name "Net-(R2-Pad2)") (class "Default")
      (node (ref "R2") (pin "2") (pinfunction "2_2") (pintype "passive"))
      (node (ref "R45") (pin "2") (pinfunction "2_2") (pintype "passive"))
      (node (ref "R5") (pin "2") (pinfunction "2_2") (pintype "passive"))
      (node (ref "U$1") (pin "IN+") (pinfunction "IN+_IN+") (pintype "bidirectional"))
    )
    (net (code "56") (name "Net-(R25-Pad2)") (class "Default")
      (node (ref "R25") (pin "2") (pinfunction "2_2") (pintype "passive"))
      (node (ref "S3") (pin "P$13") (pinfunction "3_P$13") (pintype "passive"))
      (node (ref "S3") (pin "P$14") (pinfunction "4_P$14") (pintype "passive"))
      (node (ref "S3") (pin "P$23") (pinfunction "3_P$23") (pintype "passive"))
      (node (ref "S3") (pin "P$24") (pinfunction "4_P$24") (pintype "passive"))
      (node (ref "S3") (pin "P$3") (pinfunction "3_P$3") (pintype "passive"))
      (node (ref "S3") (pin "P$4") (pinfunction "4_P$4") (pintype "passive"))
    )
    (net (code "57") (name "Net-(SG1-1)") (class "Default")
      (node (ref "C14") (pin "1") (pinfunction "1_1") (pintype "passive"))
      (node (ref "C9") (pin "1") (pinfunction "1_1") (pintype "passive"))
      (node (ref "R31") (pin "2") (pinfunction "2_2") (pintype "passive"))
      (node (ref "SG1") (pin "+") (pinfunction "1_+") (pintype "passive"))
    )
    (net (code "58") (name "Net-(SG1-2)") (class "Default")
      (node (ref "C15") (pin "1") (pinfunction "1_1") (pintype "passive"))
      (node (ref "C9") (pin "2") (pinfunction "2_2") (pintype "passive"))
      (node (ref "R32") (pin "1") (pinfunction "1_1") (pintype "passive"))
      (node (ref "SG1") (pin "-") (pinfunction "2_-") (pintype "passive"))
    )
    (net (code "59") (name "Net-(T1-PadE)") (class "Default")
      (node (ref "T1") (pin "E") (pinfunction "E_E") (pintype "passive"))
      (node (ref "T3") (pin "E") (pinfunction "E_E") (pintype "passive"))
    )
    (net (code "60") (name "ON_OFF_PIN") (class "Default")
      (node (ref "44") (pin "2") (pinfunction "2_2") (pintype "passive"))
      (node (ref "U3") (pin "24") (pinfunction "PC2_24") (pintype "bidirectional"))
    )
    (net (code "61") (name "OUT_A") (class "Default")
      (node (ref "U1") (pin "11") (pinfunction "A_11") (pintype "bidirectional"))
      (node (ref "U3") (pin "37") (pinfunction "PA3_37") (pintype "bidirectional"))
    )
    (net (code "62") (name "OUT_B") (class "Default")
      (node (ref "U1") (pin "10") (pinfunction "B_10") (pintype "bidirectional"))
      (node (ref "U3") (pin "38") (pinfunction "PA2_38") (pintype "bidirectional"))
    )
    (net (code "63") (name "OUT_C") (class "Default")
      (node (ref "U1") (pin "9") (pinfunction "C_9") (pintype "bidirectional"))
      (node (ref "U3") (pin "39") (pinfunction "PA1_39") (pintype "bidirectional"))
    )
    (net (code "64") (name "P2") (class "Default")
      (node (ref "BH10") (pin "M1") (pinfunction "-_M1") (pintype "power_in"))
      (node (ref "BH10") (pin "M2") (pinfunction "-_M2") (pintype "power_in"))
      (node (ref "BH10") (pin "M3") (pinfunction "-_M3") (pintype "power_in"))
      (node (ref "BH10") (pin "M4") (pinfunction "-_M4") (pintype "power_in"))
      (node (ref "BH12") (pin "M1") (pinfunction "-_M1") (pintype "power_in"))
      (node (ref "BH12") (pin "M2") (pinfunction "-_M2") (pintype "power_in"))
      (node (ref "BH12") (pin "M3") (pinfunction "-_M3") (pintype "power_in"))
      (node (ref "BH12") (pin "M4") (pinfunction "-_M4") (pintype "power_in"))
    )
    (net (code "65") (name "P3") (class "Default")
      (node (ref "BH11") (pin "P1") (pinfunction "+_P1") (pintype "power_in"))
      (node (ref "BH11") (pin "P2") (pinfunction "+_P2") (pintype "power_in"))
      (node (ref "BH11") (pin "P3") (pinfunction "+_P3") (pintype "power_in"))
      (node (ref "BH11") (pin "P4") (pinfunction "+_P4") (pintype "power_in"))
      (node (ref "BH9") (pin "P1") (pinfunction "+_P1") (pintype "power_in"))
      (node (ref "BH9") (pin "P2") (pinfunction "+_P2") (pintype "power_in"))
      (node (ref "BH9") (pin "P3") (pinfunction "+_P3") (pintype "power_in"))
      (node (ref "BH9") (pin "P4") (pinfunction "+_P4") (pintype "power_in"))
    )
    (net (code "66") (name "PWM") (class "Default")
      (node (ref "R48") (pin "1") (pinfunction "1_1") (pintype "passive"))
    )
    (net (code "67") (name "R_") (class "Default")
      (node (ref "C18") (pin "1") (pinfunction "1_1") (pintype "passive"))
      (node (ref "R1") (pin "2") (pinfunction "2_2") (pintype "passive"))
      (node (ref "T1") (pin "B") (pinfunction "B_B") (pintype "passive"))
    )
    (net (code "68") (name "VCC") (class "Default")
      (node (ref "C1") (pin "1") (pinfunction "1_1") (pintype "passive"))
      (node (ref "C16") (pin "3") (pinfunction "1_3") (pintype "passive"))
      (node (ref "C17") (pin "1") (pinfunction "1_1") (pintype "passive"))
      (node (ref "C2") (pin "1") (pinfunction "1_1") (pintype "passive"))
      (node (ref "C3") (pin "1") (pinfunction "1_1") (pintype "passive"))
      (node (ref "D5") (pin "C") (pinfunction "C_C") (pintype "passive"))
      (node (ref "D7") (pin "A") (pinfunction "A_A") (pintype "passive"))
      (node (ref "D8") (pin "C") (pinfunction "C_C") (pintype "passive"))
      (node (ref "IC1") (pin "3") (pinfunction "VO_3") (pintype "passive"))
      (node (ref "JP1") (pin "5") (pinfunction "VCC_5") (pintype "passive"))
      (node (ref "M2") (pin "2") (pinfunction "S_2") (pintype "passive"))
      (node (ref "R1") (pin "1") (pinfunction "1_1") (pintype "passive"))
      (node (ref "R21") (pin "1") (pinfunction "1_1") (pintype "passive"))
      (node (ref "R22") (pin "1") (pinfunction "1_1") (pintype "passive"))
      (node (ref "R28") (pin "1") (pinfunction "1_1") (pintype "passive"))
      (node (ref "R4") (pin "1") (pinfunction "1_1") (pintype "passive"))
      (node (ref "R50") (pin "2") (pinfunction "2_2") (pintype "passive"))
      (node (ref "R7") (pin "2") (pinfunction "2_2") (pintype "passive"))
      (node (ref "T1") (pin "C") (pinfunction "C_C") (pintype "passive"))
      (node (ref "T2") (pin "E") (pinfunction "E_E") (pintype "passive"))
      (node (ref "U$3") (pin "VOUT") (pinfunction "VOUT_VOUT") (pintype "bidirectional"))
      (node (ref "U2") (pin "3") (pinfunction "VDD_3") (pintype "power_in"))
      (node (ref "U3") (pin "10") (pinfunction "VCC_10") (pintype "power_in"))
      (node (ref "U4") (pin "5") (pinfunction "OUT_5") (pintype "passive"))
    )
    (net (code "69") (name "VCC_IN") (class "Default")
      (node (ref "JP6") (pin "P3") (pinfunction "3_P3") (pintype "passive"))
      (node (ref "JP6") (pin "P3A") (pinfunction "3_P3A") (pintype "passive"))
      (node (ref "R20") (pin "2") (pinfunction "2_2") (pintype "passive"))
    )
    (net (code "70") (name "VIN_P") (class "Default")
      (node (ref "47") (pin "2") (pinfunction "2_2") (pintype "passive"))
      (node (ref "C6") (pin "2") (pinfunction "2_2") (pintype "passive"))
      (node (ref "D10") (pin "A") (pinfunction "A_A") (pintype "passive"))
      (node (ref "D9") (pin "A") (pinfunction "A_A") (pintype "passive"))
      (node (ref "R2") (pin "1") (pinfunction "1_1") (pintype "passive"))
      (node (ref "R45") (pin "1") (pinfunction "1_1") (pintype "passive"))
      (node (ref "R5") (pin "1") (pinfunction "1_1") (pintype "passive"))
    )
    (net (code "71") (name "V_IN") (class "Default")
      (node (ref "BH7") (pin "P1") (pinfunction "+_P1") (pintype "power_in"))
      (node (ref "BH7") (pin "P2") (pinfunction "+_P2") (pintype "power_in"))
      (node (ref "BH7") (pin "P3") (pinfunction "+_P3") (pintype "power_in"))
      (node (ref "BH7") (pin "P4") (pinfunction "+_P4") (pintype "power_in"))
      (node (ref "C13") (pin "2") (pinfunction "2_2") (pintype "passive"))
      (node (ref "C19") (pin "1") (pinfunction "1_1") (pintype "passive"))
      (node (ref "D3") (pin "C") (pinfunction "C_C") (pintype "passive"))
      (node (ref "D7") (pin "C") (pinfunction "C_C") (pintype "passive"))
      (node (ref "D9") (pin "C") (pinfunction "C_C") (pintype "passive"))
      (node (ref "IC1") (pin "2@1") (pinfunction "VI1_2@1") (pintype "input"))
      (node (ref "M3") (pin "2") (pinfunction "S_2") (pintype "passive"))
      (node (ref "R33") (pin "2") (pinfunction "2_2") (pintype "passive"))
      (node (ref "R34") (pin "2") (pinfunction "2_2") (pintype "passive"))
      (node (ref "S3") (pin "P$1") (pinfunction "1_P$1") (pintype "passive"))
      (node (ref "S3") (pin "P$11") (pinfunction "1_P$11") (pintype "passive"))
      (node (ref "S3") (pin "P$12") (pinfunction "2_P$12") (pintype "passive"))
      (node (ref "S3") (pin "P$15") (pinfunction "5_P$15") (pintype "passive"))
      (node (ref "S3") (pin "P$2") (pinfunction "2_P$2") (pintype "passive"))
      (node (ref "S3") (pin "P$21") (pinfunction "1_P$21") (pintype "passive"))
      (node (ref "S3") (pin "P$22") (pinfunction "2_P$22") (pintype "passive"))
      (node (ref "T2") (pin "B") (pinfunction "B_B") (pintype "passive"))
      (node (ref "T2") (pin "C") (pinfunction "C_C") (pintype "passive"))
      (node (ref "U$1") (pin "B+") (pinfunction "B+_B+") (pintype "bidirectional"))
      (node (ref "U$1") (pin "OUT+") (pinfunction "OUT+_OUT+") (pintype "bidirectional"))
      (node (ref "U$3") (pin "VIN") (pinfunction "VIN_VIN") (pintype "bidirectional"))
      (node (ref "U1") (pin "16") (pinfunction "VDD_16") (pintype "bidirectional"))
      (node (ref "U4") (pin "1") (pinfunction "IN_1") (pintype "input"))
    )
    (net (code "72") (name "XTAL1") (class "Default")
      (node (ref "C8") (pin "1") (pinfunction "1_1") (pintype "passive"))
      (node (ref "U3") (pin "13") (pinfunction "XTAL1_13") (pintype "input"))
      (node (ref "Y2") (pin "1") (pinfunction "1_1") (pintype "passive"))
    )
    (net (code "73") (name "XTAL2") (class "Default")
      (node (ref "C7") (pin "1") (pinfunction "1_1") (pintype "passive"))
      (node (ref "U3") (pin "12") (pinfunction "XTAL2_12") (pintype "output"))
      (node (ref "Y2") (pin "2") (pinfunction "2_2") (pintype "passive"))
    )
    (net (code "74") (name "XX_3") (class "Default")
      (node (ref "46") (pin "1") (pinfunction "1_1") (pintype "passive"))
      (node (ref "D10") (pin "C") (pinfunction "C_C") (pintype "passive"))
      (node (ref "D8") (pin "A") (pinfunction "A_A") (pintype "passive"))
      (node (ref "M12") (pin "2") (pinfunction "S_2") (pintype "passive"))
      (node (ref "R20") (pin "1") (pinfunction "1_1") (pintype "passive"))
    )
    (net (code "75") (name "unconnected-(IC1-VI-Pad2)") (class "Default")
      (node (ref "IC1") (pin "2") (pinfunction "VI_2") (pintype "input"))
    )
    (net (code "76") (name "{slash}RESET") (class "Default")
      (node (ref "JP1") (pin "P$1") (pinfunction "RST_P$1") (pintype "passive"))
      (node (ref "R6") (pin "1") (pinfunction "1_1") (pintype "passive"))
      (node (ref "T3") (pin "C") (pinfunction "C_C") (pintype "passive"))
      (node (ref "U3") (pin "9") (pinfunction "~{RESET}_9") (pintype "input"))
    )
  )
)
